# SCH_Dashboy_subboard_2023-03-21.net
KiCad netlist of a schematic drawn in EasyEDA
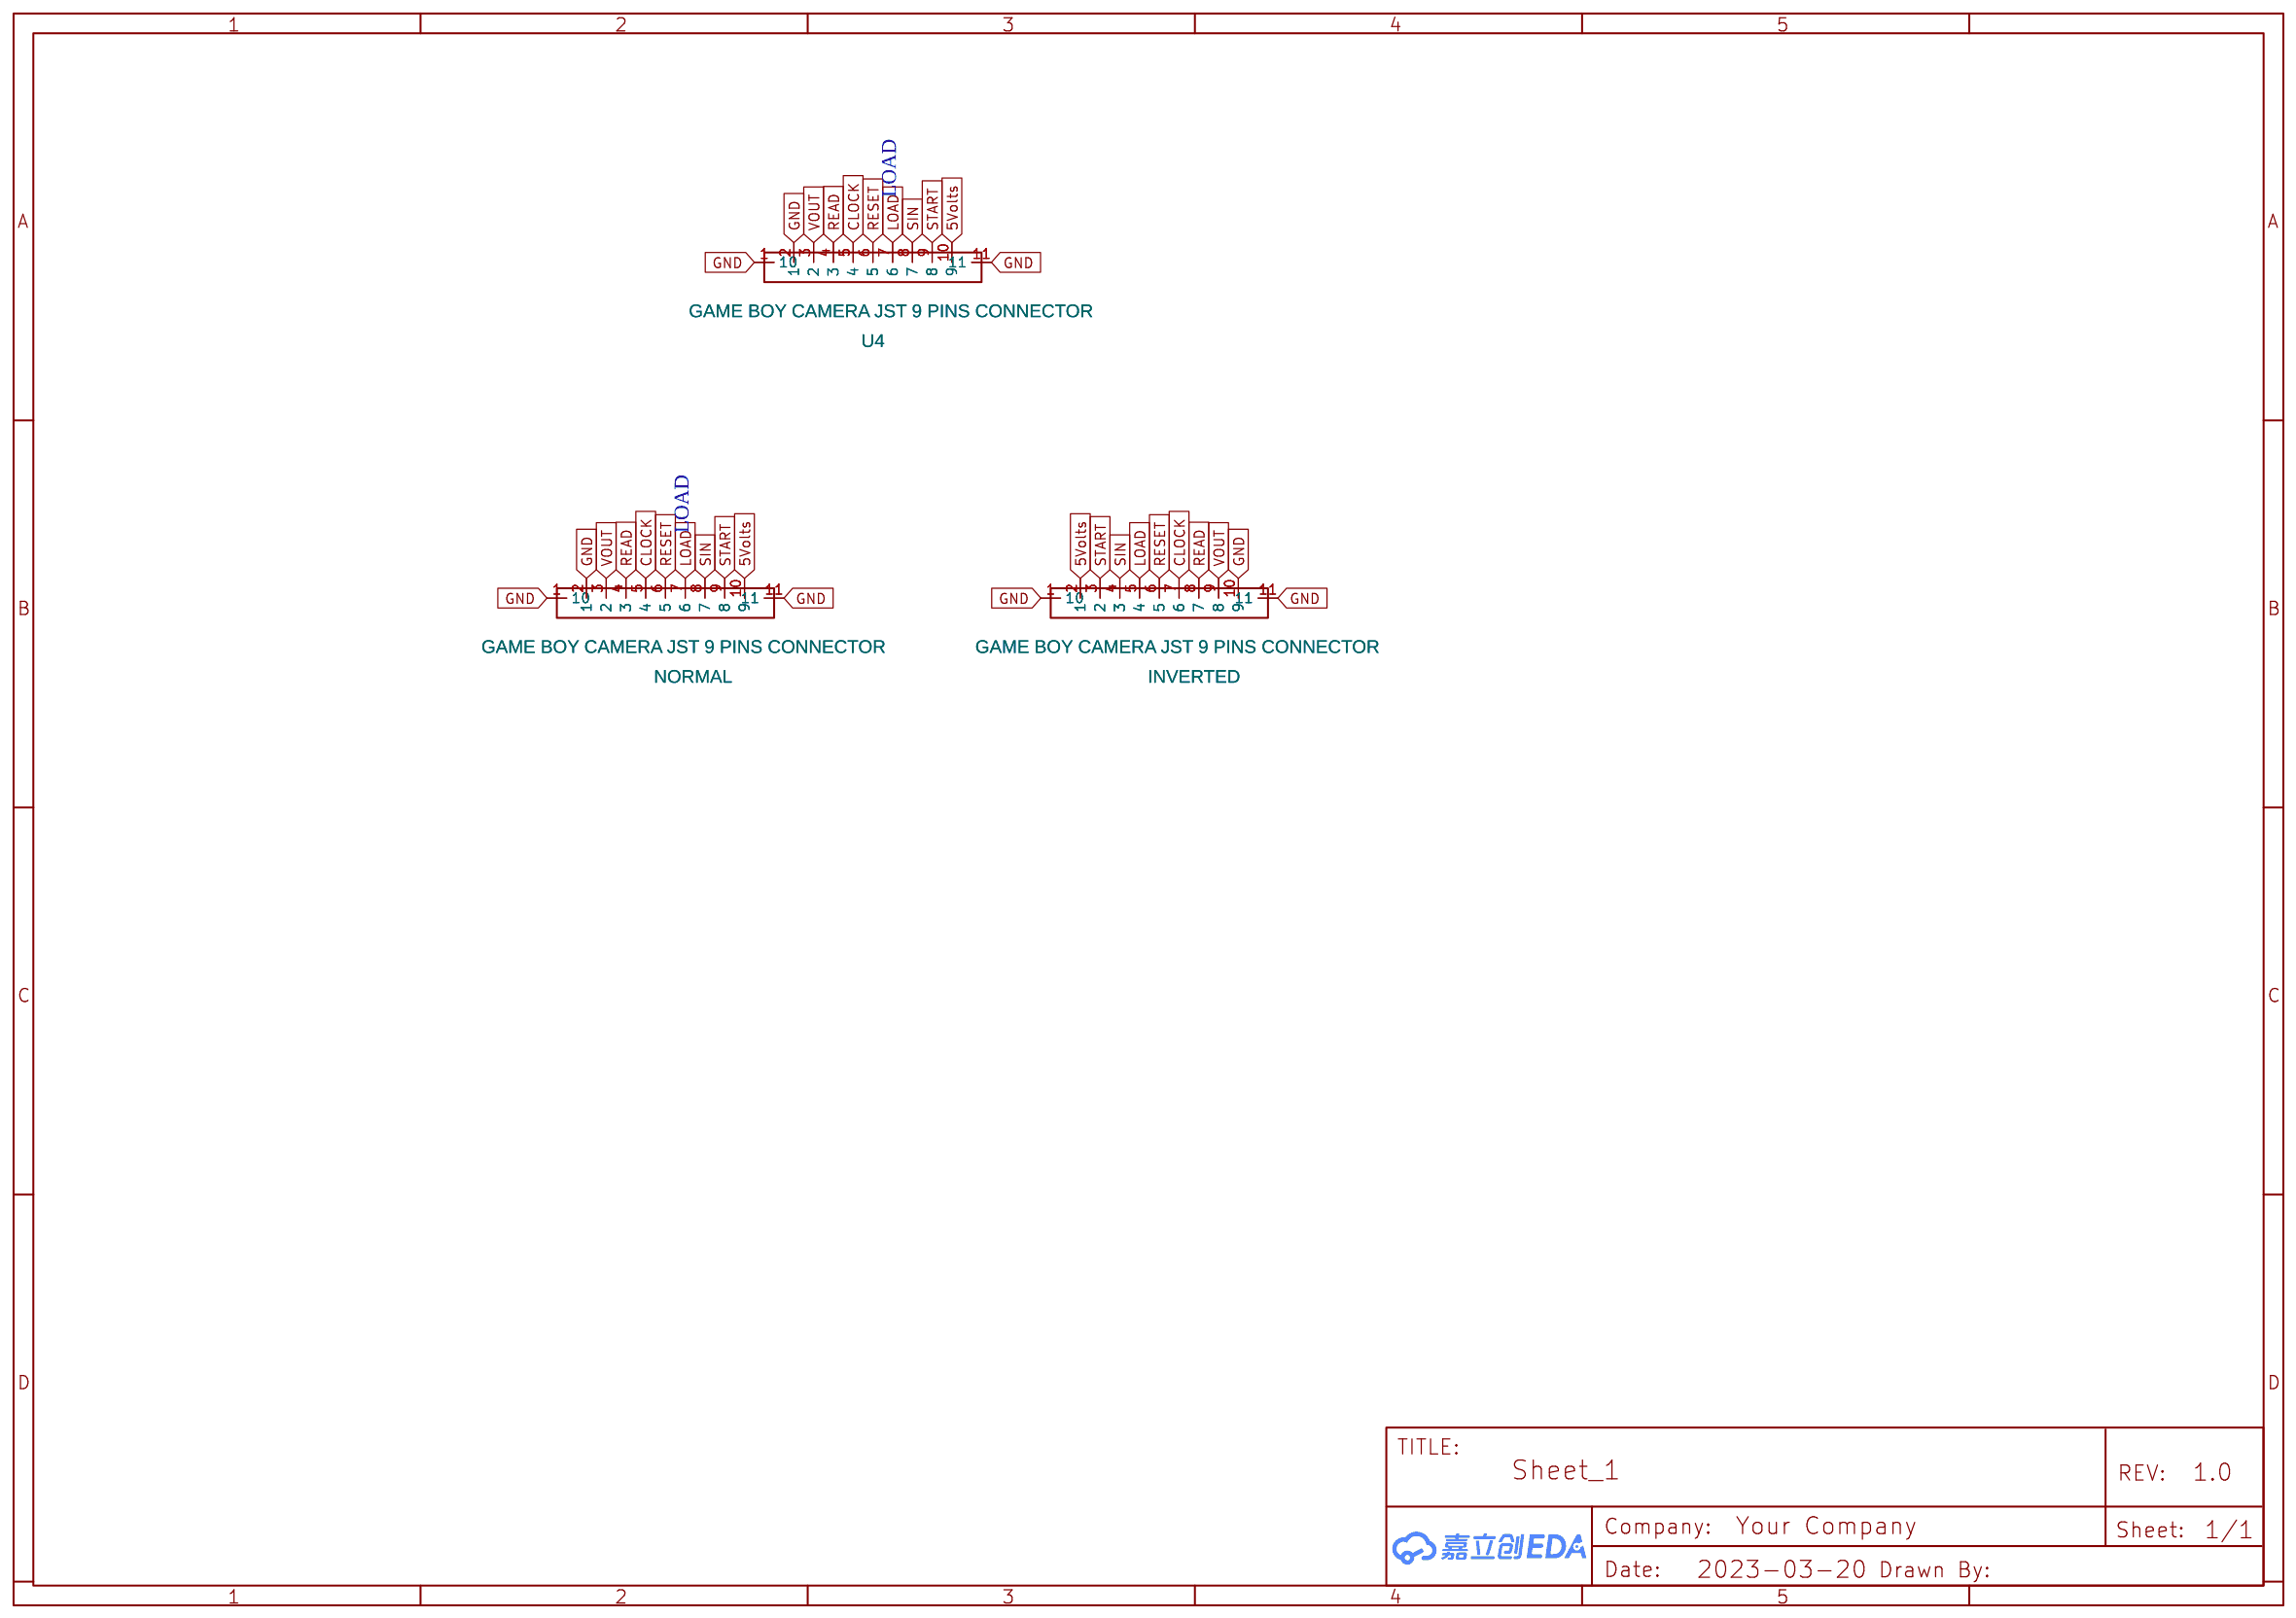
[diagram p0: schematic sheet]

(export (version "E")
  (design (tool "Eeschema 10.0.6"))
  (components
    (comp (ref "INVERTED")
      (value "GAME BOY CAMERA JST 9 PINS CONNECTOR")
      (libsource (lib "") (part "GAME BOY CAMERA JST 9 PINS CONNECTOR_2"))
    )
    (comp (ref "NORMAL")
      (value "GAME BOY CAMERA JST 9 PINS CONNECTOR")
      (libsource (lib "") (part "GAME BOY CAMERA JST 9 PINS CONNECTOR_1"))
    )
    (comp (ref "U4")
      (value "GAME BOY CAMERA JST 9 PINS CONNECTOR")
      (libsource (lib "") (part "GAME BOY CAMERA JST 9 PINS CONNECTOR"))
    )
  )
  (nets
    (net (code "1") (name "5Volts") (class "Default")
      (node (ref "INVERTED") (pin "2") (pinfunction "1_2") (pintype "unspecified"))
      (node (ref "NORMAL") (pin "10") (pinfunction "9_10") (pintype "unspecified"))
      (node (ref "U4") (pin "10") (pinfunction "9_10") (pintype "unspecified"))
    )
    (net (code "2") (name "CLOCK") (class "Default")
      (node (ref "INVERTED") (pin "7") (pinfunction "6_7") (pintype "unspecified"))
      (node (ref "NORMAL") (pin "5") (pinfunction "4_5") (pintype "unspecified"))
      (node (ref "U4") (pin "5") (pinfunction "4_5") (pintype "unspecified"))
    )
    (net (code "3") (name "GND") (class "Default")
      (node (ref "INVERTED") (pin "1") (pinfunction "10_1") (pintype "unspecified"))
      (node (ref "INVERTED") (pin "10") (pinfunction "9_10") (pintype "unspecified"))
      (node (ref "INVERTED") (pin "11") (pinfunction "11_11") (pintype "unspecified"))
      (node (ref "NORMAL") (pin "1") (pinfunction "10_1") (pintype "unspecified"))
      (node (ref "NORMAL") (pin "11") (pinfunction "11_11") (pintype "unspecified"))
      (node (ref "NORMAL") (pin "2") (pinfunction "1_2") (pintype "unspecified"))
      (node (ref "U4") (pin "1") (pinfunction "10_1") (pintype "unspecified"))
      (node (ref "U4") (pin "11") (pinfunction "11_11") (pintype "unspecified"))
      (node (ref "U4") (pin "2") (pinfunction "1_2") (pintype "unspecified"))
    )
    (net (code "4") (name "LOAD") (class "Default")
      (node (ref "INVERTED") (pin "5") (pinfunction "4_5") (pintype "unspecified"))
      (node (ref "NORMAL") (pin "7") (pinfunction "6_7") (pintype "unspecified"))
      (node (ref "U4") (pin "7") (pinfunction "6_7") (pintype "unspecified"))
    )
    (net (code "5") (name "READ") (class "Default")
      (node (ref "INVERTED") (pin "8") (pinfunction "7_8") (pintype "unspecified"))
      (node (ref "NORMAL") (pin "4") (pinfunction "3_4") (pintype "unspecified"))
      (node (ref "U4") (pin "4") (pinfunction "3_4") (pintype "unspecified"))
    )
    (net (code "6") (name "RESET") (class "Default")
      (node (ref "INVERTED") (pin "6") (pinfunction "5_6") (pintype "unspecified"))
      (node (ref "NORMAL") (pin "6") (pinfunction "5_6") (pintype "unspecified"))
      (node (ref "U4") (pin "6") (pinfunction "5_6") (pintype "unspecified"))
    )
    (net (code "7") (name "SIN") (class "Default")
      (node (ref "INVERTED") (pin "4") (pinfunction "3_4") (pintype "unspecified"))
      (node (ref "NORMAL") (pin "8") (pinfunction "7_8") (pintype "unspecified"))
      (node (ref "U4") (pin "8") (pinfunction "7_8") (pintype "unspecified"))
    )
    (net (code "8") (name "START") (class "Default")
      (node (ref "INVERTED") (pin "3") (pinfunction "2_3") (pintype "unspecified"))
      (node (ref "NORMAL") (pin "9") (pinfunction "8_9") (pintype "unspecified"))
      (node (ref "U4") (pin "9") (pinfunction "8_9") (pintype "unspecified"))
    )
    (net (code "9") (name "VOUT") (class "Default")
      (node (ref "INVERTED") (pin "9") (pinfunction "8_9") (pintype "unspecified"))
      (node (ref "NORMAL") (pin "3") (pinfunction "2_3") (pintype "unspecified"))
      (node (ref "U4") (pin "3") (pinfunction "2_3") (pintype "unspecified"))
    )
  )
)
